# X-Bot.net
KiCad netlist of a schematic drawn in Altium Designer
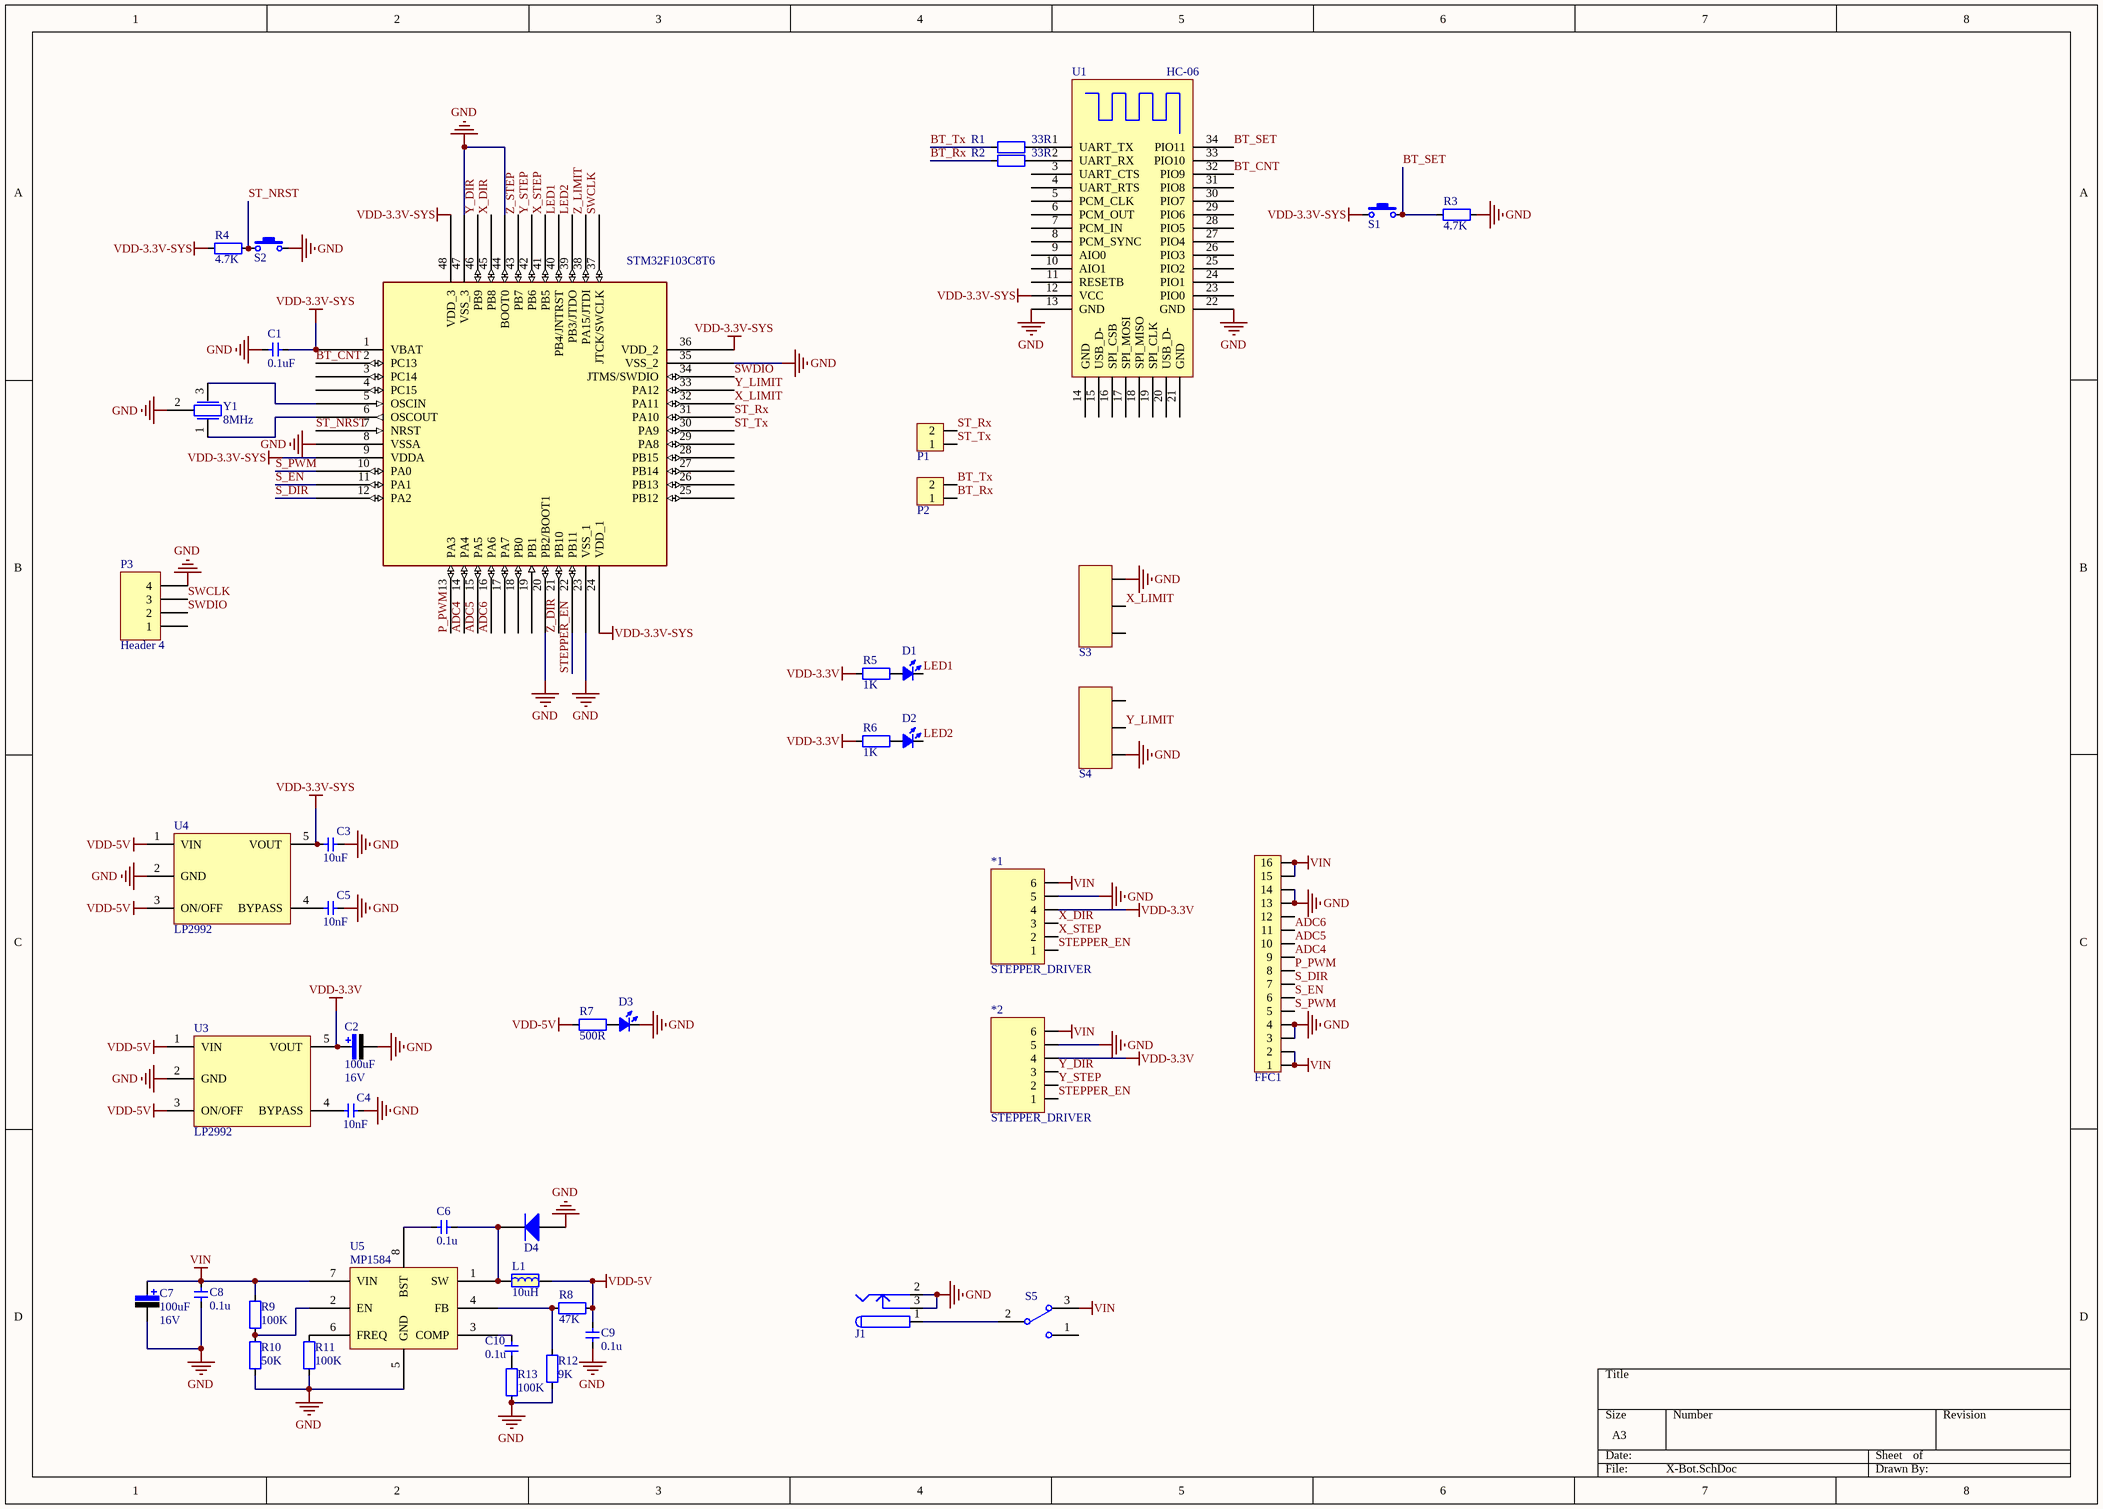
[diagram p0: X-Bot.SchDoc]

(export (version "E")
  (design (tool "Eeschema 10.0.6"))
  (components
    (comp (ref "*1")
      (value "STEPPER_DRIVER")
      (footprint "STEPPER_DRIVER")
      (libsource (lib "mLib") (part "STEPPER_DRIVER"))
    )
    (comp (ref "*2")
      (value "STEPPER_DRIVER")
      (footprint "STEPPER_DRIVER")
      (libsource (lib "mLib") (part "STEPPER_DRIVER"))
    )
    (comp (ref "C1")
      (value "0.1uF")
      (footprint "mLib:0603-CAP")
      (description "Capacitor")
      (libsource (lib "mLib") (part "电容-0603"))
    )
    (comp (ref "C2")
      (value "100uF")
      (footprint "3528-CAP")
      (description "极性电解电容")
      (fields
        (field (name "VOL") "16V")
        (field (name "Comment") "电容 3528")
        (field (name "PUBLISHER") "Altium Limited")
      )
      (libsource (lib "") (part "电容 3528_1"))
    )
    (comp (ref "C3")
      (value "10uF")
      (footprint "mLib:0603-CAP")
      (description "Capacitor")
      (fields (field (name "Comment") "10nF"))
      (libsource (lib "mLib") (part "电容-0603"))
    )
    (comp (ref "C4")
      (value "10nF")
      (footprint "mLib:0603-CAP")
      (description "Capacitor")
      (libsource (lib "mLib") (part "电容-0603"))
    )
    (comp (ref "C5")
      (value "10nF")
      (footprint "mLib:0603-CAP")
      (description "Capacitor")
      (libsource (lib "mLib") (part "电容-0603"))
    )
    (comp (ref "C6")
      (value "0.1u")
      (footprint "mLib:0603-CAP")
      (description "Capacitor")
      (fields (field (name "Comment") "电容-0603"))
      (libsource (lib "mLib") (part "电容-0603"))
    )
    (comp (ref "C7")
      (value "100uF")
      (footprint "3528-CAP")
      (description "极性电解电容")
      (fields
        (field (name "VOL") "16V")
        (field (name "Comment") "电容 3528")
        (field (name "PUBLISHER") "Altium Limited")
      )
      (libsource (lib "mLib") (part "电容 3528"))
    )
    (comp (ref "C8")
      (value "0.1u")
      (footprint "mLib:0603-CAP")
      (description "Capacitor")
      (fields (field (name "Comment") "电容-0603"))
      (libsource (lib "mLib") (part "电容-0603"))
    )
    (comp (ref "C9")
      (value "0.1u")
      (footprint "mLib:0603-CAP")
      (description "Capacitor")
      (fields (field (name "Comment") "电容-0603"))
      (libsource (lib "mLib") (part "电容-0603"))
    )
    (comp (ref "C10")
      (value "0.1u")
      (footprint "mLib:0603-CAP")
      (description "Capacitor")
      (fields (field (name "Comment") "电容-0603"))
      (libsource (lib "mLib") (part "电容-0603"))
    )
    (comp (ref "D1")
      (value "LED-0603")
      (footprint "mLib:0603-LED-BLUE")
      (description "LED")
      (libsource (lib "mLib") (part "LED-0603"))
    )
    (comp (ref "D2")
      (value "LED-0603")
      (footprint "mLib:0603-LED-BLUE")
      (description "LED")
      (libsource (lib "mLib") (part "LED-0603"))
    )
    (comp (ref "D3")
      (value "LED-0603")
      (footprint "mLib:0603-LED-BLUE")
      (description "LED")
      (libsource (lib "mLib") (part "LED-0603"))
    )
    (comp (ref "D4")
      (value "二极管-5819W")
      (footprint "SOD-123")
      (description "40V")
      (libsource (lib "mLib") (part "二极管-5819W"))
    )
    (comp (ref "FFC1")
      (value "FFC_0.5_16")
      (footprint "FFC_0.5_16")
      (description "FFC")
      (libsource (lib "Integrated_Library") (part "FFC_0.5_16"))
    )
    (comp (ref "J1")
      (value "PowerJack_2.5")
      (footprint "KLD_0202")
      (description "DC Power Jack")
      (libsource (lib "Integrated_Library") (part "PowerJack_2.5"))
    )
    (comp (ref "L1")
      (value "10uH")
      (footprint "L-SMD-7")
      (description "磁珠")
      (libsource (lib "mLib") (part "电感-0805"))
    )
    (comp (ref "P1")
      (value "HDR1x2_2.54")
      (footprint "HDR1X2_2.54_180")
      (description "Header")
      (libsource (lib "Integrated_Library") (part "HDR1x2_2.54"))
    )
    (comp (ref "P2")
      (value "HDR1x2_2.54")
      (footprint "HDR1X2_2.54_180")
      (description "Header")
      (libsource (lib "Integrated_Library") (part "HDR1x2_2.54"))
    )
    (comp (ref "P3")
      (value "Header 4")
      (footprint "HDR1X4")
      (description "Header, 4-Pin")
      (fields (field (name "PUBLISHER") "Altium Limited"))
      (libsource (lib "Miscellaneous Connectors") (part "Header 4"))
    )
    (comp (ref "R1")
      (value "33R")
      (footprint "mLib:0603-RES")
      (description "Resistor")
      (fields (field (name "Comment") "500R"))
      (libsource (lib "mLib") (part "电阻-0603"))
    )
    (comp (ref "R2")
      (value "33R")
      (footprint "mLib:0603-RES")
      (description "Resistor")
      (fields (field (name "Comment") "500R"))
      (libsource (lib "mLib") (part "电阻-0603"))
    )
    (comp (ref "R3")
      (value "4.7K")
      (footprint "mLib:0603-RES")
      (description "Resistor")
      (libsource (lib "") (part "电阻-0603_1"))
    )
    (comp (ref "R4")
      (value "4.7K")
      (footprint "mLib:0603-RES")
      (description "Resistor")
      (libsource (lib "") (part "电阻-0603_1"))
    )
    (comp (ref "R5")
      (value "1K")
      (footprint "mLib:0603-RES")
      (description "Resistor")
      (fields (field (name "Comment") "500R"))
      (libsource (lib "mLib") (part "电阻-0603"))
    )
    (comp (ref "R6")
      (value "1K")
      (footprint "mLib:0603-RES")
      (description "Resistor")
      (fields (field (name "Comment") "500R"))
      (libsource (lib "mLib") (part "电阻-0603"))
    )
    (comp (ref "R7")
      (value "500R")
      (footprint "mLib:0603-RES")
      (description "Resistor")
      (libsource (lib "mLib") (part "电阻-0603"))
    )
    (comp (ref "R8")
      (value "47K")
      (footprint "mLib:0603-RES")
      (description "Resistor")
      (fields (field (name "Comment") "100K"))
      (libsource (lib "") (part "电阻-0603_1"))
    )
    (comp (ref "R9")
      (value "100K")
      (footprint "mLib:0603-RES")
      (description "Resistor")
      (libsource (lib "") (part "电阻-0603_2"))
    )
    (comp (ref "R10")
      (value "50K")
      (footprint "mLib:0603-RES")
      (description "Resistor")
      (fields (field (name "Comment") "100K"))
      (libsource (lib "") (part "电阻-0603_2"))
    )
    (comp (ref "R11")
      (value "100K")
      (footprint "mLib:0603-RES")
      (description "Resistor")
      (libsource (lib "") (part "电阻-0603_2"))
    )
    (comp (ref "R12")
      (value "9K")
      (footprint "mLib:0603-RES")
      (description "Resistor")
      (fields (field (name "Comment") "100K"))
      (libsource (lib "") (part "电阻-0603_2"))
    )
    (comp (ref "R13")
      (value "100K")
      (footprint "mLib:0603-RES")
      (description "Resistor")
      (libsource (lib "") (part "电阻-0603_2"))
    )
    (comp (ref "S1")
      (value "ButtonTACT_3x4x2_180")
      (footprint "ButtonTACT_3x4x2_180H")
      (description "Button")
      (libsource (lib "Integrated_Library") (part "ButtonTACT_3x4x2_180"))
    )
    (comp (ref "S2")
      (value "ButtonTACT_3x4x2_180")
      (footprint "ButtonTACT_3x4x2_180H")
      (description "Button")
      (libsource (lib "Integrated_Library") (part "ButtonTACT_3x4x2_180"))
    )
    (comp (ref "S3")
      (value "LimitSwitch")
      (footprint "Limit Switch")
      (libsource (lib "mLib") (part "LimitSwitch"))
    )
    (comp (ref "S4")
      (value "LimitSwitch")
      (footprint "Limit Switch")
      (libsource (lib "mLib") (part "LimitSwitch"))
    )
    (comp (ref "S5")
      (value "SwitchSPDT_4.3x8.6_D90")
      (footprint "SwitchSPDT_4.3X8.6_D90")
      (description "Switch")
      (libsource (lib "Integrated_Library") (part "SwitchSPDT_4.3x8.6_D90"))
    )
    (comp (ref "U1")
      (value "HC-06")
      (footprint "蓝牙模块HC-06")
      (description "HM bluetooth module HM-01,HM-02,HM-09")
      (libsource (lib "HMSoft") (part "HM01_02_09_1"))
    )
    (comp (ref "U2")
      (value "STM32F103C8T6")
      (footprint "LQFP-48")
      (description "MCU")
      (libsource (lib "mLib") (part "STM32F103C8T6"))
    )
    (comp (ref "U3")
      (value "LP2992")
      (footprint "SOT23-5")
      (description "LDO")
      (libsource (lib "mLib") (part "LP2992"))
    )
    (comp (ref "U4")
      (value "LP2992")
      (footprint "SOT23-5")
      (description "LDO")
      (libsource (lib "mLib") (part "LP2992"))
    )
    (comp (ref "U5")
      (value "MP1584")
      (footprint "SO-8")
      (description "电源芯片")
      (libsource (lib "mLib") (part "MP1584"))
    )
    (comp (ref "Y1")
      (value "8MHz")
      (footprint "晶振-3P")
      (description "村田贴片")
      (libsource (lib "mLib") (part "晶振-3Pin"))
    )
  )
  (nets
    (net (code "1") (name "/ADC4") (class "Default")
      (node (ref "FFC1") (pin "9") (pinfunction "9_9") (pintype "passive"))
      (node (ref "U2") (pin "14") (pinfunction "PA4_14") (pintype "bidirectional"))
    )
    (net (code "2") (name "/ADC5") (class "Default")
      (node (ref "FFC1") (pin "10") (pinfunction "10_10") (pintype "passive"))
      (node (ref "U2") (pin "15") (pinfunction "PA5_15") (pintype "bidirectional"))
    )
    (net (code "3") (name "/ADC6") (class "Default")
      (node (ref "FFC1") (pin "11") (pinfunction "11_11") (pintype "passive"))
      (node (ref "U2") (pin "16") (pinfunction "PA6_16") (pintype "bidirectional"))
    )
    (net (code "4") (name "/BT_CNT") (class "Default")
      (node (ref "U1") (pin "32") (pinfunction "PIO9_32") (pintype "passive"))
      (node (ref "U2") (pin "2") (pinfunction "PC13_2") (pintype "bidirectional"))
    )
    (net (code "5") (name "/BT_Rx") (class "Default")
      (node (ref "P2") (pin "1") (pinfunction "1_1") (pintype "passive"))
      (node (ref "R2") (pin "1") (pinfunction "1_1") (pintype "passive"))
    )
    (net (code "6") (name "/BT_SET") (class "Default")
      (node (ref "R3") (pin "2") (pinfunction "2_2") (pintype "passive"))
      (node (ref "S1") (pin "2") (pinfunction "2_2") (pintype "passive"))
      (node (ref "U1") (pin "34") (pinfunction "PIO11_34") (pintype "passive"))
    )
    (net (code "7") (name "/BT_Tx") (class "Default")
      (node (ref "P2") (pin "2") (pinfunction "2_2") (pintype "passive"))
      (node (ref "R1") (pin "1") (pinfunction "1_1") (pintype "passive"))
    )
    (net (code "8") (name "/LED1") (class "Default")
      (node (ref "D1") (pin "2") (pinfunction "K_2") (pintype "passive"))
      (node (ref "U2") (pin "40") (pinfunction "PB4/JNTRST_40") (pintype "bidirectional"))
    )
    (net (code "9") (name "/LED2") (class "Default")
      (node (ref "D2") (pin "2") (pinfunction "K_2") (pintype "passive"))
      (node (ref "U2") (pin "39") (pinfunction "PB3/JTDO_39") (pintype "bidirectional"))
    )
    (net (code "10") (name "/P_PWM") (class "Default")
      (node (ref "FFC1") (pin "8") (pinfunction "8_8") (pintype "passive"))
      (node (ref "U2") (pin "13") (pinfunction "PA3_13") (pintype "bidirectional"))
    )
    (net (code "11") (name "/STEPPER_EN") (class "Default")
      (node (ref "*1") (pin "1") (pinfunction "1_1") (pintype "passive"))
      (node (ref "*2") (pin "1") (pinfunction "1_1") (pintype "passive"))
      (node (ref "U2") (pin "22") (pinfunction "PB11_22") (pintype "bidirectional"))
    )
    (net (code "12") (name "/ST_NRST") (class "Default")
      (node (ref "R4") (pin "1") (pinfunction "1_1") (pintype "passive"))
      (node (ref "S2") (pin "1") (pinfunction "1_1") (pintype "passive"))
      (node (ref "U2") (pin "7") (pinfunction "NRST_7") (pintype "input"))
    )
    (net (code "13") (name "/ST_Rx") (class "Default")
      (node (ref "P1") (pin "2") (pinfunction "2_2") (pintype "passive"))
      (node (ref "U2") (pin "31") (pinfunction "PA10_31") (pintype "bidirectional"))
    )
    (net (code "14") (name "/ST_Tx") (class "Default")
      (node (ref "P1") (pin "1") (pinfunction "1_1") (pintype "passive"))
      (node (ref "U2") (pin "30") (pinfunction "PA9_30") (pintype "bidirectional"))
    )
    (net (code "15") (name "/SWCLK") (class "Default")
      (node (ref "P3") (pin "3") (pinfunction "3_3") (pintype "passive"))
      (node (ref "U2") (pin "37") (pinfunction "JTCK/SWCLK_37") (pintype "bidirectional"))
    )
    (net (code "16") (name "/SWDIO") (class "Default")
      (node (ref "P3") (pin "2") (pinfunction "2_2") (pintype "passive"))
      (node (ref "U2") (pin "34") (pinfunction "JTMS/SWDIO_34") (pintype "bidirectional"))
    )
    (net (code "17") (name "/S_DIR") (class "Default")
      (node (ref "FFC1") (pin "7") (pinfunction "7_7") (pintype "passive"))
      (node (ref "U2") (pin "12") (pinfunction "PA2_12") (pintype "bidirectional"))
    )
    (net (code "18") (name "/S_EN") (class "Default")
      (node (ref "FFC1") (pin "6") (pinfunction "6_6") (pintype "passive"))
      (node (ref "U2") (pin "11") (pinfunction "PA1_11") (pintype "bidirectional"))
    )
    (net (code "19") (name "/S_PWM") (class "Default")
      (node (ref "FFC1") (pin "5") (pinfunction "5_5") (pintype "passive"))
      (node (ref "U2") (pin "10") (pinfunction "PA0_10") (pintype "bidirectional"))
    )
    (net (code "20") (name "/X_DIR") (class "Default")
      (node (ref "*1") (pin "3") (pinfunction "3_3") (pintype "passive"))
      (node (ref "U2") (pin "45") (pinfunction "PB8_45") (pintype "bidirectional"))
    )
    (net (code "21") (name "/X_LIMIT") (class "Default")
      (node (ref "S3") (pin "2") (pintype "power_in"))
      (node (ref "U2") (pin "32") (pinfunction "PA11_32") (pintype "bidirectional"))
    )
    (net (code "22") (name "/X_STEP") (class "Default")
      (node (ref "*1") (pin "2") (pinfunction "2_2") (pintype "passive"))
      (node (ref "U2") (pin "41") (pinfunction "PB5_41") (pintype "bidirectional"))
    )
    (net (code "23") (name "/Y_DIR") (class "Default")
      (node (ref "*2") (pin "3") (pinfunction "3_3") (pintype "passive"))
      (node (ref "U2") (pin "46") (pinfunction "PB9_46") (pintype "bidirectional"))
    )
    (net (code "24") (name "/Y_LIMIT") (class "Default")
      (node (ref "S4") (pin "2") (pintype "power_in"))
      (node (ref "U2") (pin "33") (pinfunction "PA12_33") (pintype "bidirectional"))
    )
    (net (code "25") (name "/Y_STEP") (class "Default")
      (node (ref "*2") (pin "2") (pinfunction "2_2") (pintype "passive"))
      (node (ref "U2") (pin "42") (pinfunction "PB6_42") (pintype "bidirectional"))
    )
    (net (code "26") (name "/Z_DIR") (class "Default")
      (node (ref "U2") (pin "21") (pinfunction "PB10_21") (pintype "bidirectional"))
    )
    (net (code "27") (name "/Z_LIMIT") (class "Default")
      (node (ref "U2") (pin "38") (pinfunction "PA15/JTDI_38") (pintype "bidirectional"))
    )
    (net (code "28") (name "/Z_STEP") (class "Default")
      (node (ref "U2") (pin "43") (pinfunction "PB7_43") (pintype "bidirectional"))
    )
    (net (code "29") (name "GND") (class "Default")
      (node (ref "*1") (pin "5") (pinfunction "5_5") (pintype "passive"))
      (node (ref "*2") (pin "5") (pinfunction "5_5") (pintype "passive"))
      (node (ref "C1") (pin "1") (pinfunction "1_1") (pintype "passive"))
      (node (ref "C2") (pin "2") (pinfunction "2_2") (pintype "passive"))
      (node (ref "C3") (pin "1") (pinfunction "1_1") (pintype "passive"))
      (node (ref "C4") (pin "1") (pinfunction "1_1") (pintype "passive"))
      (node (ref "C5") (pin "1") (pinfunction "1_1") (pintype "passive"))
      (node (ref "C7") (pin "2") (pinfunction "2_2") (pintype "passive"))
      (node (ref "C8") (pin "1") (pinfunction "1_1") (pintype "passive"))
      (node (ref "C9") (pin "2") (pinfunction "2_2") (pintype "passive"))
      (node (ref "D3") (pin "2") (pinfunction "K_2") (pintype "passive"))
      (node (ref "D4") (pin "1") (pinfunction "A_1") (pintype "passive"))
      (node (ref "FFC1") (pin "13") (pinfunction "13_13") (pintype "passive"))
      (node (ref "FFC1") (pin "14") (pinfunction "14_14") (pintype "passive"))
      (node (ref "FFC1") (pin "3") (pinfunction "3_3") (pintype "passive"))
      (node (ref "FFC1") (pin "4") (pinfunction "4_4") (pintype "passive"))
      (node (ref "J1") (pin "2") (pinfunction "2_2") (pintype "power_in"))
      (node (ref "J1") (pin "3") (pinfunction "3_3") (pintype "power_in"))
      (node (ref "P3") (pin "4") (pinfunction "4_4") (pintype "passive"))
      (node (ref "R10") (pin "1") (pinfunction "1_1") (pintype "passive"))
      (node (ref "R11") (pin "1") (pinfunction "1_1") (pintype "passive"))
      (node (ref "R12") (pin "1") (pinfunction "1_1") (pintype "passive"))
      (node (ref "R13") (pin "1") (pinfunction "1_1") (pintype "passive"))
      (node (ref "R3") (pin "1") (pinfunction "1_1") (pintype "passive"))
      (node (ref "S2") (pin "2") (pinfunction "2_2") (pintype "passive"))
      (node (ref "S3") (pin "3") (pintype "power_in"))
      (node (ref "S4") (pin "1") (pintype "power_in"))
      (node (ref "U1") (pin "13") (pinfunction "GND_13") (pintype "passive"))
      (node (ref "U1") (pin "22") (pinfunction "GND_22") (pintype "passive"))
      (node (ref "U2") (pin "20") (pinfunction "PB2/BOOT1_20") (pintype "bidirectional"))
      (node (ref "U2") (pin "23") (pinfunction "VSS_1_23") (pintype "power_in"))
      (node (ref "U2") (pin "35") (pinfunction "VSS_2_35") (pintype "power_in"))
      (node (ref "U2") (pin "44") (pinfunction "BOOT0_44") (pintype "bidirectional"))
      (node (ref "U2") (pin "47") (pinfunction "VSS_3_47") (pintype "power_in"))
      (node (ref "U2") (pin "8") (pinfunction "VSSA_8") (pintype "power_in"))
      (node (ref "U3") (pin "2") (pinfunction "GND_2") (pintype "passive"))
      (node (ref "U4") (pin "2") (pinfunction "GND_2") (pintype "passive"))
      (node (ref "U5") (pin "5") (pinfunction "GND_5") (pintype "passive"))
      (node (ref "Y1") (pin "2") (pinfunction "2_2") (pintype "passive"))
    )
    (net (code "30") (name "Net-(C10-Pad1)") (class "Default")
      (node (ref "C10") (pin "1") (pinfunction "1_1") (pintype "passive"))
      (node (ref "R13") (pin "2") (pinfunction "2_2") (pintype "passive"))
    )
    (net (code "31") (name "Net-(D1-A)") (class "Default")
      (node (ref "D1") (pin "1") (pinfunction "A_1") (pintype "passive"))
      (node (ref "R5") (pin "2") (pinfunction "2_2") (pintype "passive"))
    )
    (net (code "32") (name "Net-(D2-A)") (class "Default")
      (node (ref "D2") (pin "1") (pinfunction "A_1") (pintype "passive"))
      (node (ref "R6") (pin "2") (pinfunction "2_2") (pintype "passive"))
    )
    (net (code "33") (name "Net-(D3-A)") (class "Default")
      (node (ref "D3") (pin "1") (pinfunction "A_1") (pintype "passive"))
      (node (ref "R7") (pin "2") (pinfunction "2_2") (pintype "passive"))
    )
    (net (code "34") (name "Net-(D4-K)") (class "Default")
      (node (ref "C6") (pin "2") (pinfunction "2_2") (pintype "passive"))
      (node (ref "D4") (pin "2") (pinfunction "K_2") (pintype "passive"))
      (node (ref "L1") (pin "1") (pintype "passive"))
      (node (ref "U5") (pin "1") (pinfunction "SW_1") (pintype "passive"))
    )
    (net (code "35") (name "Net-(J1-Pad1)") (class "Default")
      (node (ref "J1") (pin "1") (pinfunction "1_1") (pintype "power_in"))
      (node (ref "S5") (pin "2") (pinfunction "2_2") (pintype "passive"))
    )
    (net (code "36") (name "Net-(U1-UART_RX)") (class "Default")
      (node (ref "R2") (pin "2") (pinfunction "2_2") (pintype "passive"))
      (node (ref "U1") (pin "2") (pinfunction "UART_RX_2") (pintype "passive"))
    )
    (net (code "37") (name "Net-(U1-UART_TX)") (class "Default")
      (node (ref "R1") (pin "2") (pinfunction "2_2") (pintype "passive"))
      (node (ref "U1") (pin "1") (pinfunction "UART_TX_1") (pintype "passive"))
    )
    (net (code "38") (name "Net-(U2-OSCIN)") (class "Default")
      (node (ref "U2") (pin "5") (pinfunction "OSCIN_5") (pintype "input"))
      (node (ref "Y1") (pin "3") (pinfunction "3_3") (pintype "passive"))
    )
    (net (code "39") (name "Net-(U2-OSCOUT)") (class "Default")
      (node (ref "U2") (pin "6") (pinfunction "OSCOUT_6") (pintype "output"))
      (node (ref "Y1") (pin "1") (pinfunction "1_1") (pintype "passive"))
    )
    (net (code "40") (name "Net-(U3-BYPASS)") (class "Default")
      (node (ref "C4") (pin "2") (pinfunction "2_2") (pintype "passive"))
      (node (ref "U3") (pin "4") (pinfunction "BYPASS_4") (pintype "passive"))
    )
    (net (code "41") (name "Net-(U4-BYPASS)") (class "Default")
      (node (ref "C5") (pin "2") (pinfunction "2_2") (pintype "passive"))
      (node (ref "U4") (pin "4") (pinfunction "BYPASS_4") (pintype "passive"))
    )
    (net (code "42") (name "Net-(U5-BST)") (class "Default")
      (node (ref "C6") (pin "1") (pinfunction "1_1") (pintype "passive"))
      (node (ref "U5") (pin "8") (pinfunction "BST_8") (pintype "passive"))
    )
    (net (code "43") (name "Net-(U5-COMP)") (class "Default")
      (node (ref "C10") (pin "2") (pinfunction "2_2") (pintype "passive"))
      (node (ref "U5") (pin "3") (pinfunction "COMP_3") (pintype "passive"))
    )
    (net (code "44") (name "Net-(U5-EN)") (class "Default")
      (node (ref "R10") (pin "2") (pinfunction "2_2") (pintype "passive"))
      (node (ref "R9") (pin "1") (pinfunction "1_1") (pintype "passive"))
      (node (ref "U5") (pin "2") (pinfunction "EN_2") (pintype "passive"))
    )
    (net (code "45") (name "Net-(U5-FB)") (class "Default")
      (node (ref "R12") (pin "2") (pinfunction "2_2") (pintype "passive"))
      (node (ref "R8") (pin "2") (pinfunction "2_2") (pintype "passive"))
      (node (ref "U5") (pin "4") (pinfunction "FB_4") (pintype "passive"))
    )
    (net (code "46") (name "Net-(U5-FREQ)") (class "Default")
      (node (ref "R11") (pin "2") (pinfunction "2_2") (pintype "passive"))
      (node (ref "U5") (pin "6") (pinfunction "FREQ_6") (pintype "passive"))
    )
    (net (code "47") (name "VDD-3.3V") (class "Default")
      (node (ref "*1") (pin "4") (pinfunction "4_4") (pintype "passive"))
      (node (ref "*2") (pin "4") (pinfunction "4_4") (pintype "passive"))
      (node (ref "C2") (pin "1") (pinfunction "1_1") (pintype "passive"))
      (node (ref "R5") (pin "1") (pinfunction "1_1") (pintype "passive"))
      (node (ref "R6") (pin "1") (pinfunction "1_1") (pintype "passive"))
      (node (ref "U3") (pin "5") (pinfunction "VOUT_5") (pintype "passive"))
    )
    (net (code "48") (name "VDD-3.3V-SYS") (class "Default")
      (node (ref "C1") (pin "2") (pinfunction "2_2") (pintype "passive"))
      (node (ref "C3") (pin "2") (pinfunction "2_2") (pintype "passive"))
      (node (ref "R4") (pin "2") (pinfunction "2_2") (pintype "passive"))
      (node (ref "S1") (pin "1") (pinfunction "1_1") (pintype "passive"))
      (node (ref "U1") (pin "12") (pinfunction "VCC_12") (pintype "passive"))
      (node (ref "U2") (pin "1") (pinfunction "VBAT_1") (pintype "power_in"))
      (node (ref "U2") (pin "24") (pinfunction "VDD_1_24") (pintype "power_in"))
      (node (ref "U2") (pin "36") (pinfunction "VDD_2_36") (pintype "power_in"))
      (node (ref "U2") (pin "48") (pinfunction "VDD_3_48") (pintype "power_in"))
      (node (ref "U2") (pin "9") (pinfunction "VDDA_9") (pintype "power_in"))
      (node (ref "U4") (pin "5") (pinfunction "VOUT_5") (pintype "passive"))
    )
    (net (code "49") (name "VDD-5V") (class "Default")
      (node (ref "C9") (pin "1") (pinfunction "1_1") (pintype "passive"))
      (node (ref "L1") (pin "2") (pinfunction "2_2") (pintype "passive"))
      (node (ref "R7") (pin "1") (pinfunction "1_1") (pintype "passive"))
      (node (ref "R8") (pin "1") (pinfunction "1_1") (pintype "passive"))
      (node (ref "U3") (pin "1") (pinfunction "VIN_1") (pintype "passive"))
      (node (ref "U3") (pin "3") (pinfunction "ON/OFF_3") (pintype "passive"))
      (node (ref "U4") (pin "1") (pinfunction "VIN_1") (pintype "passive"))
      (node (ref "U4") (pin "3") (pinfunction "ON/OFF_3") (pintype "passive"))
    )
    (net (code "50") (name "VIN") (class "Default")
      (node (ref "*1") (pin "6") (pinfunction "6_6") (pintype "passive"))
      (node (ref "*2") (pin "6") (pinfunction "6_6") (pintype "passive"))
      (node (ref "C7") (pin "1") (pinfunction "1_1") (pintype "passive"))
      (node (ref "C8") (pin "2") (pinfunction "2_2") (pintype "passive"))
      (node (ref "FFC1") (pin "1") (pinfunction "1_1") (pintype "passive"))
      (node (ref "FFC1") (pin "15") (pinfunction "15_15") (pintype "passive"))
      (node (ref "FFC1") (pin "16") (pinfunction "16_16") (pintype "passive"))
      (node (ref "FFC1") (pin "2") (pinfunction "2_2") (pintype "passive"))
      (node (ref "R9") (pin "2") (pinfunction "2_2") (pintype "passive"))
      (node (ref "S5") (pin "3") (pinfunction "3_3") (pintype "passive"))
      (node (ref "U5") (pin "7") (pinfunction "VIN_7") (pintype "passive"))
    )
    (net (code "51") (name "unconnected-(FFC1-Pad12)") (class "Default")
      (node (ref "FFC1") (pin "12") (pinfunction "12_12") (pintype "passive"))
    )
    (net (code "52") (name "unconnected-(P3-Pad1)") (class "Default")
      (node (ref "P3") (pin "1") (pinfunction "1_1") (pintype "passive"))
    )
    (net (code "53") (name "unconnected-(S3-Pad1)") (class "Default")
      (node (ref "S3") (pin "1") (pintype "power_in"))
    )
    (net (code "54") (name "unconnected-(S4-Pad3)") (class "Default")
      (node (ref "S4") (pin "3") (pintype "power_in"))
    )
    (net (code "55") (name "unconnected-(S5-Pad1)") (class "Default")
      (node (ref "S5") (pin "1") (pinfunction "1_1") (pintype "passive"))
    )
    (net (code "56") (name "unconnected-(U1-AIO0-Pad9)") (class "Default")
      (node (ref "U1") (pin "9") (pinfunction "AIO0_9") (pintype "passive"))
    )
    (net (code "57") (name "unconnected-(U1-AIO1-Pad10)") (class "Default")
      (node (ref "U1") (pin "10") (pinfunction "AIO1_10") (pintype "passive"))
    )
    (net (code "58") (name "unconnected-(U1-GND-Pad14)") (class "Default")
      (node (ref "U1") (pin "14") (pinfunction "GND_14") (pintype "passive"))
    )
    (net (code "59") (name "unconnected-(U1-GND-Pad21)") (class "Default")
      (node (ref "U1") (pin "21") (pinfunction "GND_21") (pintype "passive"))
    )
    (net (code "60") (name "unconnected-(U1-PCM_CLK-Pad5)") (class "Default")
      (node (ref "U1") (pin "5") (pinfunction "PCM_CLK_5") (pintype "passive"))
    )
    (net (code "61") (name "unconnected-(U1-PCM_IN-Pad7)") (class "Default")
      (node (ref "U1") (pin "7") (pinfunction "PCM_IN_7") (pintype "passive"))
    )
    (net (code "62") (name "unconnected-(U1-PCM_OUT-Pad6)") (class "Default")
      (node (ref "U1") (pin "6") (pinfunction "PCM_OUT_6") (pintype "passive"))
    )
    (net (code "63") (name "unconnected-(U1-PCM_SYNC-Pad8)") (class "Default")
      (node (ref "U1") (pin "8") (pinfunction "PCM_SYNC_8") (pintype "passive"))
    )
    (net (code "64") (name "unconnected-(U1-PIO0-Pad23)") (class "Default")
      (node (ref "U1") (pin "23") (pinfunction "PIO0_23") (pintype "passive"))
    )
    (net (code "65") (name "unconnected-(U1-PIO1-Pad24)") (class "Default")
      (node (ref "U1") (pin "24") (pinfunction "PIO1_24") (pintype "passive"))
    )
    (net (code "66") (name "unconnected-(U1-PIO2-Pad25)") (class "Default")
      (node (ref "U1") (pin "25") (pinfunction "PIO2_25") (pintype "passive"))
    )
    (net (code "67") (name "unconnected-(U1-PIO3-Pad26)") (class "Default")
      (node (ref "U1") (pin "26") (pinfunction "PIO3_26") (pintype "passive"))
    )
    (net (code "68") (name "unconnected-(U1-PIO4-Pad27)") (class "Default")
      (node (ref "U1") (pin "27") (pinfunction "PIO4_27") (pintype "passive"))
    )
    (net (code "69") (name "unconnected-(U1-PIO5-Pad28)") (class "Default")
      (node (ref "U1") (pin "28") (pinfunction "PIO5_28") (pintype "passive"))
    )
    (net (code "70") (name "unconnected-(U1-PIO6-Pad29)") (class "Default")
      (node (ref "U1") (pin "29") (pinfunction "PIO6_29") (pintype "passive"))
    )
    (net (code "71") (name "unconnected-(U1-PIO7-Pad30)") (class "Default")
      (node (ref "U1") (pin "30") (pinfunction "PIO7_30") (pintype "passive"))
    )
    (net (code "72") (name "unconnected-(U1-PIO8-Pad31)") (class "Default")
      (node (ref "U1") (pin "31") (pinfunction "PIO8_31") (pintype "passive"))
    )
    (net (code "73") (name "unconnected-(U1-PIO10-Pad33)") (class "Default")
      (node (ref "U1") (pin "33") (pinfunction "PIO10_33") (pintype "passive"))
    )
    (net (code "74") (name "unconnected-(U1-RESETB-Pad11)") (class "Default")
      (node (ref "U1") (pin "11") (pinfunction "RESETB_11") (pintype "passive"))
    )
    (net (code "75") (name "unconnected-(U1-SPI_CLK-Pad19)") (class "Default")
      (node (ref "U1") (pin "19") (pinfunction "SPI_CLK_19") (pintype "passive"))
    )
    (net (code "76") (name "unconnected-(U1-SPI_CSB-Pad16)") (class "Default")
      (node (ref "U1") (pin "16") (pinfunction "SPI_CSB_16") (pintype "passive"))
    )
    (net (code "77") (name "unconnected-(U1-SPI_MISO-Pad18)") (class "Default")
      (node (ref "U1") (pin "18") (pinfunction "SPI_MISO_18") (pintype "passive"))
    )
    (net (code "78") (name "unconnected-(U1-SPI_MOSI-Pad17)") (class "Default")
      (node (ref "U1") (pin "17") (pinfunction "SPI_MOSI_17") (pintype "passive"))
    )
    (net (code "79") (name "unconnected-(U1-UART_CTS-Pad3)") (class "Default")
      (node (ref "U1") (pin "3") (pinfunction "UART_CTS_3") (pintype "passive"))
    )
    (net (code "80") (name "unconnected-(U1-UART_RTS-Pad4)") (class "Default")
      (node (ref "U1") (pin "4") (pinfunction "UART_RTS_4") (pintype "passive"))
    )
    (net (code "81") (name "unconnected-(U1-USB_D--Pad15)") (class "Default")
      (node (ref "U1") (pin "15") (pinfunction "USB_D-_15") (pintype "passive"))
    )
    (net (code "82") (name "unconnected-(U1-USB_D--Pad20)") (class "Default")
      (node (ref "U1") (pin "20") (pinfunction "USB_D-_20") (pintype "passive"))
    )
    (net (code "83") (name "unconnected-(U2-PA7-Pad17)") (class "Default")
      (node (ref "U2") (pin "17") (pinfunction "PA7_17") (pintype "bidirectional"))
    )
    (net (code "84") (name "unconnected-(U2-PA8-Pad29)") (class "Default")
      (node (ref "U2") (pin "29") (pinfunction "PA8_29") (pintype "bidirectional"))
    )
    (net (code "85") (name "unconnected-(U2-PB0-Pad18)") (class "Default")
      (node (ref "U2") (pin "18") (pinfunction "PB0_18") (pintype "bidirectional"))
    )
    (net (code "86") (name "unconnected-(U2-PB1-Pad19)") (class "Default")
      (node (ref "U2") (pin "19") (pinfunction "PB1_19") (pintype "input"))
    )
    (net (code "87") (name "unconnected-(U2-PB12-Pad25)") (class "Default")
      (node (ref "U2") (pin "25") (pinfunction "PB12_25") (pintype "bidirectional"))
    )
    (net (code "88") (name "unconnected-(U2-PB13-Pad26)") (class "Default")
      (node (ref "U2") (pin "26") (pinfunction "PB13_26") (pintype "bidirectional"))
    )
    (net (code "89") (name "unconnected-(U2-PB14-Pad27)") (class "Default")
      (node (ref "U2") (pin "27") (pinfunction "PB14_27") (pintype "bidirectional"))
    )
    (net (code "90") (name "unconnected-(U2-PB15-Pad28)") (class "Default")
      (node (ref "U2") (pin "28") (pinfunction "PB15_28") (pintype "bidirectional"))
    )
    (net (code "91") (name "unconnected-(U2-PC14-Pad3)") (class "Default")
      (node (ref "U2") (pin "3") (pinfunction "PC14_3") (pintype "bidirectional"))
    )
    (net (code "92") (name "unconnected-(U2-PC15-Pad4)") (class "Default")
      (node (ref "U2") (pin "4") (pinfunction "PC15_4") (pintype "bidirectional"))
    )
  )
)
